# w65c265sxb_tms9118_dram_rev1.net
KiCad netlist of a schematic drawn in EAGLE
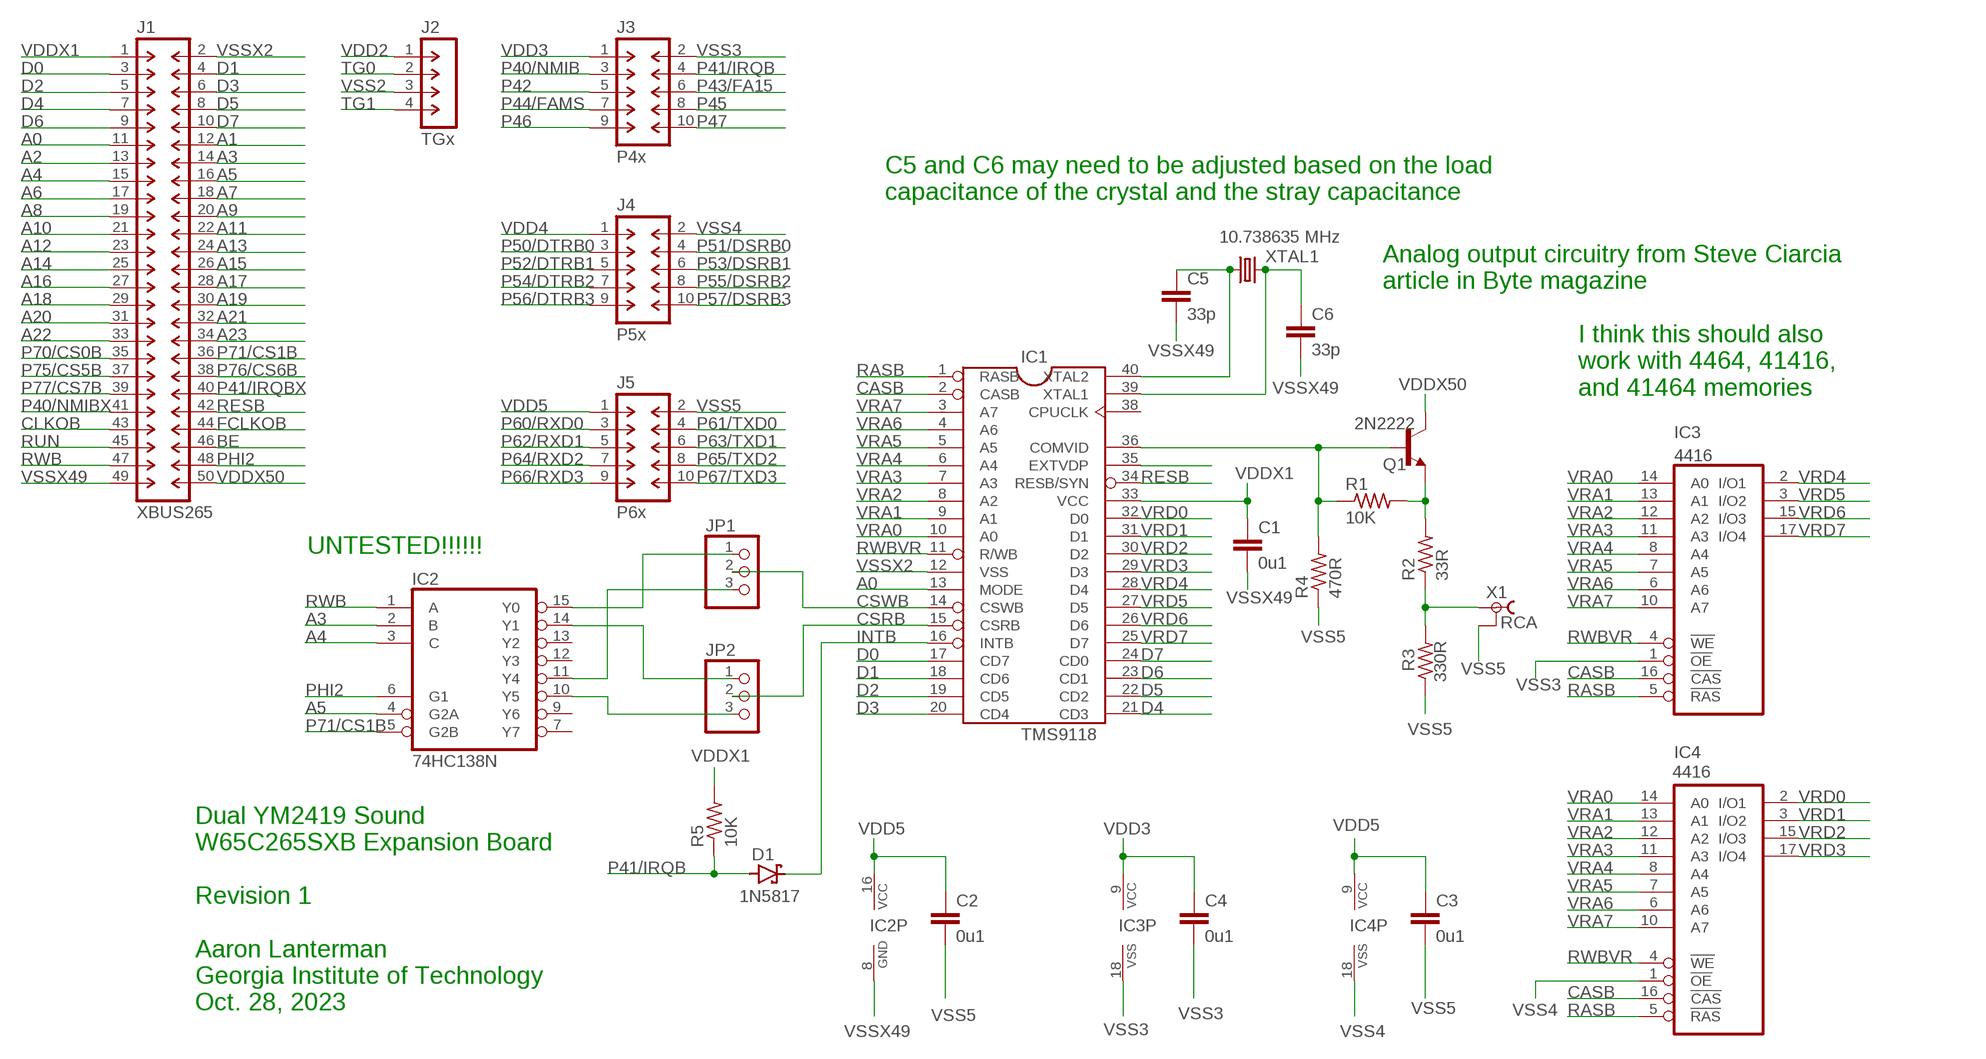
[diagram p0: schematic, sheet 1]

(export (version "E")
  (design (tool "Eeschema 10.0.6"))
  (components
    (comp (ref "C1")
      (value "0u1")
      (footprint "eagle-import:C050-025X075-AARON")
      (libsource (lib "eagle-import") (part "C-EU050-025X075-AARON"))
    )
    (comp (ref "C2")
      (value "0u1")
      (footprint "eagle-import:C050-025X075-AARON")
      (libsource (lib "eagle-import") (part "C-EU050-025X075-AARON"))
    )
    (comp (ref "C3")
      (value "0u1")
      (footprint "eagle-import:C050-025X075-AARON")
      (libsource (lib "eagle-import") (part "C-EU050-025X075-AARON"))
    )
    (comp (ref "C4")
      (value "0u1")
      (footprint "eagle-import:C050-025X075-AARON")
      (libsource (lib "eagle-import") (part "C-EU050-025X075-AARON"))
    )
    (comp (ref "C5")
      (value "33p")
      (footprint "eagle-import:C050-025X075-AARON")
      (libsource (lib "eagle-import") (part "C-EU050-025X075-AARON"))
    )
    (comp (ref "C6")
      (value "33p")
      (footprint "eagle-import:C050-025X075-AARON")
      (libsource (lib "eagle-import") (part "C-EU050-025X075-AARON"))
    )
    (comp (ref "D1")
      (value "1N5817-B")
      (footprint "eagle-import:DO41-7.6")
      (libsource (lib "eagle-import") (part "1N5817-B"))
    )
    (comp (ref "IC1")
      (value "TMS9118")
      (footprint "eagle-import:DIL40")
      (libsource (lib "eagle-import") (part "TMS9118"))
    )
    (comp (ref "IC2")
      (value "74HC138N")
      (footprint "eagle-import:DIL16")
      (libsource (lib "eagle-import") (part "74138NHC"))
    )
    (comp (ref "IC3")
      (value "41464")
      (footprint "eagle-import:DIL18")
      (libsource (lib "eagle-import") (part "41464"))
    )
    (comp (ref "IC4")
      (value "41464")
      (footprint "eagle-import:DIL18")
      (libsource (lib "eagle-import") (part "41464"))
    )
    (comp (ref "J1")
      (value "XBUS265")
      (footprint "eagle-import:DIL-100-2X25")
      (libsource (lib "eagle-import") (part "M-2X25-DIL-100"))
    )
    (comp (ref "J2")
      (value "TGx")
      (footprint "eagle-import:SIP-100-04-40")
      (libsource (lib "eagle-import") (part "M-1X04-SIP-100-40"))
    )
    (comp (ref "J3")
      (value "P4x")
      (footprint "eagle-import:DIL-100-2X05")
      (libsource (lib "eagle-import") (part "M-2X05-DIL-100"))
    )
    (comp (ref "J4")
      (value "P5x")
      (footprint "eagle-import:DIL-100-2X05")
      (libsource (lib "eagle-import") (part "M-2X05-DIL-100"))
    )
    (comp (ref "J5")
      (value "P6x")
      (footprint "eagle-import:DIL-100-2X05")
      (libsource (lib "eagle-import") (part "M-2X05-DIL-100"))
    )
    (comp (ref "JP1")
      (value "PINHD-1X3")
      (footprint "eagle-import:1X03")
      (libsource (lib "eagle-import") (part "PINHD-1X3"))
    )
    (comp (ref "JP2")
      (value "PINHD-1X3")
      (footprint "eagle-import:1X03")
      (libsource (lib "eagle-import") (part "PINHD-1X3"))
    )
    (comp (ref "Q1")
      (value "2N2222")
      (footprint "eagle-import:TO92-EBC-OVAL")
      (libsource (lib "eagle-import") (part "2N2222"))
    )
    (comp (ref "R1")
      (value "10K")
      (footprint "eagle-import:0207_10")
      (libsource (lib "eagle-import") (part "R-US_0207/10"))
    )
    (comp (ref "R2")
      (value "33R")
      (footprint "eagle-import:0207_10")
      (libsource (lib "eagle-import") (part "R-US_0207/10"))
    )
    (comp (ref "R3")
      (value "330R")
      (footprint "eagle-import:0207_10")
      (libsource (lib "eagle-import") (part "R-US_0207/10"))
    )
    (comp (ref "R4")
      (value "470R")
      (footprint "eagle-import:0207_10")
      (libsource (lib "eagle-import") (part "R-US_0207/10"))
    )
    (comp (ref "R5")
      (value "10K")
      (footprint "eagle-import:0207_10")
      (libsource (lib "eagle-import") (part "R-US_0207/10"))
    )
    (comp (ref "X1")
      (value "RCA")
      (footprint "eagle-import:TOBU3")
      (fields (field (name "MF") "FARNELL") (field (name "MPN") "TOBU 3"))
      (libsource (lib "eagle-import") (part "TOBU3"))
    )
    (comp (ref "XTAL1")
      (value "10.738635 MHz")
      (footprint "eagle-import:HC49_S")
      (libsource (lib "eagle-import") (part "CRYSTALHC49S"))
    )
  )
  (nets
    (net (code "1") (name "/A0") (class "Default")
      (node (ref "IC1") (pin "13") (pinfunction "MODE_13") (pintype "bidirectional"))
      (node (ref "J1") (pin "11") (pinfunction "11_11") (pintype "passive"))
    )
    (net (code "2") (name "/A1") (class "Default")
      (node (ref "J1") (pin "12") (pinfunction "12_12") (pintype "passive"))
    )
    (net (code "3") (name "/A2") (class "Default")
      (node (ref "J1") (pin "13") (pinfunction "13_13") (pintype "passive"))
    )
    (net (code "4") (name "/A3") (class "Default")
      (node (ref "IC2") (pin "2") (pinfunction "B_2") (pintype "input"))
      (node (ref "J1") (pin "14") (pinfunction "14_14") (pintype "passive"))
    )
    (net (code "5") (name "/A4") (class "Default")
      (node (ref "IC2") (pin "3") (pinfunction "C_3") (pintype "input"))
      (node (ref "J1") (pin "15") (pinfunction "15_15") (pintype "passive"))
    )
    (net (code "6") (name "/A5") (class "Default")
      (node (ref "IC2") (pin "4") (pinfunction "G2A_4") (pintype "input"))
      (node (ref "J1") (pin "16") (pinfunction "16_16") (pintype "passive"))
    )
    (net (code "7") (name "/A6") (class "Default")
      (node (ref "J1") (pin "17") (pinfunction "17_17") (pintype "passive"))
    )
    (net (code "8") (name "/A7") (class "Default")
      (node (ref "J1") (pin "18") (pinfunction "18_18") (pintype "passive"))
    )
    (net (code "9") (name "/A8") (class "Default")
      (node (ref "J1") (pin "19") (pinfunction "19_19") (pintype "passive"))
    )
    (net (code "10") (name "/A9") (class "Default")
      (node (ref "J1") (pin "20") (pinfunction "20_20") (pintype "passive"))
    )
    (net (code "11") (name "/A10") (class "Default")
      (node (ref "J1") (pin "21") (pinfunction "21_21") (pintype "passive"))
    )
    (net (code "12") (name "/A11") (class "Default")
      (node (ref "J1") (pin "22") (pinfunction "22_22") (pintype "passive"))
    )
    (net (code "13") (name "/A12") (class "Default")
      (node (ref "J1") (pin "23") (pinfunction "23_23") (pintype "passive"))
    )
    (net (code "14") (name "/A13") (class "Default")
      (node (ref "J1") (pin "24") (pinfunction "24_24") (pintype "passive"))
    )
    (net (code "15") (name "/A14") (class "Default")
      (node (ref "J1") (pin "25") (pinfunction "25_25") (pintype "passive"))
    )
    (net (code "16") (name "/A15") (class "Default")
      (node (ref "J1") (pin "26") (pinfunction "26_26") (pintype "passive"))
    )
    (net (code "17") (name "/A16") (class "Default")
      (node (ref "J1") (pin "27") (pinfunction "27_27") (pintype "passive"))
    )
    (net (code "18") (name "/A17") (class "Default")
      (node (ref "J1") (pin "28") (pinfunction "28_28") (pintype "passive"))
    )
    (net (code "19") (name "/A18") (class "Default")
      (node (ref "J1") (pin "29") (pinfunction "29_29") (pintype "passive"))
    )
    (net (code "20") (name "/A19") (class "Default")
      (node (ref "J1") (pin "30") (pinfunction "30_30") (pintype "passive"))
    )
    (net (code "21") (name "/A20") (class "Default")
      (node (ref "J1") (pin "31") (pinfunction "31_31") (pintype "passive"))
    )
    (net (code "22") (name "/A21") (class "Default")
      (node (ref "J1") (pin "32") (pinfunction "32_32") (pintype "passive"))
    )
    (net (code "23") (name "/A22") (class "Default")
      (node (ref "J1") (pin "33") (pinfunction "33_33") (pintype "passive"))
    )
    (net (code "24") (name "/A23") (class "Default")
      (node (ref "J1") (pin "34") (pinfunction "34_34") (pintype "passive"))
    )
    (net (code "25") (name "/BE") (class "Default")
      (node (ref "J1") (pin "46") (pinfunction "46_46") (pintype "passive"))
    )
    (net (code "26") (name "/CASB") (class "Default")
      (node (ref "IC1") (pin "2") (pinfunction "CASB_2") (pintype "bidirectional"))
      (node (ref "IC3") (pin "16") (pinfunction "~{CAS}_16") (pintype "input"))
      (node (ref "IC4") (pin "16") (pinfunction "~{CAS}_16") (pintype "input"))
    )
    (net (code "27") (name "/CLKOB") (class "Default")
      (node (ref "J1") (pin "43") (pinfunction "43_43") (pintype "passive"))
    )
    (net (code "28") (name "/CSRB") (class "Default")
      (node (ref "IC1") (pin "15") (pinfunction "CSRB_15") (pintype "bidirectional"))
      (node (ref "JP2") (pin "2") (pinfunction "2_2") (pintype "passive"))
    )
    (net (code "29") (name "/CSWB") (class "Default")
      (node (ref "IC1") (pin "14") (pinfunction "CSWB_14") (pintype "bidirectional"))
      (node (ref "JP1") (pin "2") (pinfunction "2_2") (pintype "passive"))
    )
    (net (code "30") (name "/D0") (class "Default")
      (node (ref "IC1") (pin "17") (pinfunction "CD7_17") (pintype "bidirectional"))
      (node (ref "J1") (pin "3") (pinfunction "3_3") (pintype "passive"))
    )
    (net (code "31") (name "/D1") (class "Default")
      (node (ref "IC1") (pin "18") (pinfunction "CD6_18") (pintype "bidirectional"))
      (node (ref "J1") (pin "4") (pinfunction "4_4") (pintype "passive"))
    )
    (net (code "32") (name "/D2") (class "Default")
      (node (ref "IC1") (pin "19") (pinfunction "CD5_19") (pintype "bidirectional"))
      (node (ref "J1") (pin "5") (pinfunction "5_5") (pintype "passive"))
    )
    (net (code "33") (name "/D3") (class "Default")
      (node (ref "IC1") (pin "20") (pinfunction "CD4_20") (pintype "bidirectional"))
      (node (ref "J1") (pin "6") (pinfunction "6_6") (pintype "passive"))
    )
    (net (code "34") (name "/D4") (class "Default")
      (node (ref "IC1") (pin "21") (pinfunction "CD3_21") (pintype "bidirectional"))
      (node (ref "J1") (pin "7") (pinfunction "7_7") (pintype "passive"))
    )
    (net (code "35") (name "/D5") (class "Default")
      (node (ref "IC1") (pin "22") (pinfunction "CD2_22") (pintype "bidirectional"))
      (node (ref "J1") (pin "8") (pinfunction "8_8") (pintype "passive"))
    )
    (net (code "36") (name "/D6") (class "Default")
      (node (ref "IC1") (pin "23") (pinfunction "CD1_23") (pintype "bidirectional"))
      (node (ref "J1") (pin "9") (pinfunction "9_9") (pintype "passive"))
    )
    (net (code "37") (name "/D7") (class "Default")
      (node (ref "IC1") (pin "24") (pinfunction "CD0_24") (pintype "bidirectional"))
      (node (ref "J1") (pin "10") (pinfunction "10_10") (pintype "passive"))
    )
    (net (code "38") (name "/FCLKOB") (class "Default")
      (node (ref "J1") (pin "44") (pinfunction "44_44") (pintype "passive"))
    )
    (net (code "39") (name "/INTB") (class "Default")
      (node (ref "D1") (pin "C") (pinfunction "C_C") (pintype "passive"))
      (node (ref "IC1") (pin "16") (pinfunction "INTB_16") (pintype "bidirectional"))
    )
    (net (code "40") (name "/P40{slash}NMIB") (class "Default")
      (node (ref "J3") (pin "3") (pinfunction "3_3") (pintype "passive"))
    )
    (net (code "41") (name "/P40{slash}NMIBX") (class "Default")
      (node (ref "J1") (pin "41") (pinfunction "41_41") (pintype "passive"))
    )
    (net (code "42") (name "/P41{slash}IRQB") (class "Default")
      (node (ref "D1") (pin "A") (pinfunction "A_A") (pintype "passive"))
      (node (ref "J3") (pin "4") (pinfunction "4_4") (pintype "passive"))
      (node (ref "R5") (pin "1") (pinfunction "1_1") (pintype "passive"))
    )
    (net (code "43") (name "/P41{slash}IRQBX") (class "Default")
      (node (ref "J1") (pin "40") (pinfunction "40_40") (pintype "passive"))
    )
    (net (code "44") (name "/P42") (class "Default")
      (node (ref "J3") (pin "5") (pinfunction "5_5") (pintype "passive"))
    )
    (net (code "45") (name "/P43{slash}FA15") (class "Default")
      (node (ref "J3") (pin "6") (pinfunction "6_6") (pintype "passive"))
    )
    (net (code "46") (name "/P44{slash}FAMS") (class "Default")
      (node (ref "J3") (pin "7") (pinfunction "7_7") (pintype "passive"))
    )
    (net (code "47") (name "/P45") (class "Default")
      (node (ref "J3") (pin "8") (pinfunction "8_8") (pintype "passive"))
    )
    (net (code "48") (name "/P46") (class "Default")
      (node (ref "J3") (pin "9") (pinfunction "9_9") (pintype "passive"))
    )
    (net (code "49") (name "/P47") (class "Default")
      (node (ref "J3") (pin "10") (pinfunction "10_10") (pintype "passive"))
    )
    (net (code "50") (name "/P50{slash}DTRB0") (class "Default")
      (node (ref "J4") (pin "3") (pinfunction "3_3") (pintype "passive"))
    )
    (net (code "51") (name "/P51{slash}DSRB0") (class "Default")
      (node (ref "J4") (pin "4") (pinfunction "4_4") (pintype "passive"))
    )
    (net (code "52") (name "/P52{slash}DTRB1") (class "Default")
      (node (ref "J4") (pin "5") (pinfunction "5_5") (pintype "passive"))
    )
    (net (code "53") (name "/P53{slash}DSRB1") (class "Default")
      (node (ref "J4") (pin "6") (pinfunction "6_6") (pintype "passive"))
    )
    (net (code "54") (name "/P54{slash}DTRB2") (class "Default")
      (node (ref "J4") (pin "7") (pinfunction "7_7") (pintype "passive"))
    )
    (net (code "55") (name "/P55{slash}DSRB2") (class "Default")
      (node (ref "J4") (pin "8") (pinfunction "8_8") (pintype "passive"))
    )
    (net (code "56") (name "/P56{slash}DTRB3") (class "Default")
      (node (ref "J4") (pin "9") (pinfunction "9_9") (pintype "passive"))
    )
    (net (code "57") (name "/P57{slash}DSRB3") (class "Default")
      (node (ref "J4") (pin "10") (pinfunction "10_10") (pintype "passive"))
    )
    (net (code "58") (name "/P60{slash}RXD0") (class "Default")
      (node (ref "J5") (pin "3") (pinfunction "3_3") (pintype "passive"))
    )
    (net (code "59") (name "/P61{slash}TXD0") (class "Default")
      (node (ref "J5") (pin "4") (pinfunction "4_4") (pintype "passive"))
    )
    (net (code "60") (name "/P62{slash}RXD1") (class "Default")
      (node (ref "J5") (pin "5") (pinfunction "5_5") (pintype "passive"))
    )
    (net (code "61") (name "/P63{slash}TXD1") (class "Default")
      (node (ref "J5") (pin "6") (pinfunction "6_6") (pintype "passive"))
    )
    (net (code "62") (name "/P64{slash}RXD2") (class "Default")
      (node (ref "J5") (pin "7") (pinfunction "7_7") (pintype "passive"))
    )
    (net (code "63") (name "/P65{slash}TXD2") (class "Default")
      (node (ref "J5") (pin "8") (pinfunction "8_8") (pintype "passive"))
    )
    (net (code "64") (name "/P66{slash}RXD3") (class "Default")
      (node (ref "J5") (pin "9") (pinfunction "9_9") (pintype "passive"))
    )
    (net (code "65") (name "/P67{slash}TXD3") (class "Default")
      (node (ref "J5") (pin "10") (pinfunction "10_10") (pintype "passive"))
    )
    (net (code "66") (name "/P70{slash}CS0B") (class "Default")
      (node (ref "J1") (pin "35") (pinfunction "35_35") (pintype "passive"))
    )
    (net (code "67") (name "/P71{slash}CS1B") (class "Default")
      (node (ref "IC2") (pin "5") (pinfunction "G2B_5") (pintype "input"))
      (node (ref "J1") (pin "36") (pinfunction "36_36") (pintype "passive"))
    )
    (net (code "68") (name "/P75{slash}CS5B") (class "Default")
      (node (ref "J1") (pin "37") (pinfunction "37_37") (pintype "passive"))
    )
    (net (code "69") (name "/P76{slash}CS6B") (class "Default")
      (node (ref "J1") (pin "38") (pinfunction "38_38") (pintype "passive"))
    )
    (net (code "70") (name "/P77{slash}CS7B") (class "Default")
      (node (ref "J1") (pin "39") (pinfunction "39_39") (pintype "passive"))
    )
    (net (code "71") (name "/PHI2") (class "Default")
      (node (ref "IC2") (pin "6") (pinfunction "G1_6") (pintype "input"))
      (node (ref "J1") (pin "48") (pinfunction "48_48") (pintype "passive"))
    )
    (net (code "72") (name "/RASB") (class "Default")
      (node (ref "IC1") (pin "1") (pinfunction "RASB_1") (pintype "bidirectional"))
      (node (ref "IC3") (pin "5") (pinfunction "~{RAS}_5") (pintype "input"))
      (node (ref "IC4") (pin "5") (pinfunction "~{RAS}_5") (pintype "input"))
    )
    (net (code "73") (name "/RESB") (class "Default")
      (node (ref "IC1") (pin "34") (pinfunction "RESB/SYN_34") (pintype "bidirectional"))
      (node (ref "J1") (pin "42") (pinfunction "42_42") (pintype "passive"))
    )
    (net (code "74") (name "/RUN") (class "Default")
      (node (ref "J1") (pin "45") (pinfunction "45_45") (pintype "passive"))
    )
    (net (code "75") (name "/RWB") (class "Default")
      (node (ref "IC2") (pin "1") (pinfunction "A_1") (pintype "input"))
      (node (ref "J1") (pin "47") (pinfunction "47_47") (pintype "passive"))
    )
    (net (code "76") (name "/RWBVR") (class "Default")
      (node (ref "IC1") (pin "11") (pinfunction "R/WB_11") (pintype "bidirectional"))
      (node (ref "IC3") (pin "4") (pinfunction "~{WE}_4") (pintype "input"))
      (node (ref "IC4") (pin "4") (pinfunction "~{WE}_4") (pintype "input"))
    )
    (net (code "77") (name "/TG0") (class "Default")
      (node (ref "J2") (pin "2") (pinfunction "2_2") (pintype "passive"))
    )
    (net (code "78") (name "/TG1") (class "Default")
      (node (ref "J2") (pin "4") (pinfunction "4_4") (pintype "passive"))
    )
    (net (code "79") (name "/VDD2") (class "Default")
      (node (ref "J2") (pin "1") (pinfunction "1_1") (pintype "passive"))
    )
    (net (code "80") (name "/VDD3") (class "Default")
      (node (ref "C4") (pin "1") (pinfunction "1_1") (pintype "passive"))
      (node (ref "IC3") (pin "9") (pinfunction "VCC_9") (pintype "power_in"))
      (node (ref "J3") (pin "1") (pinfunction "1_1") (pintype "passive"))
    )
    (net (code "81") (name "/VDD4") (class "Default")
      (node (ref "J4") (pin "1") (pinfunction "1_1") (pintype "passive"))
    )
    (net (code "82") (name "/VDD5") (class "Default")
      (node (ref "C2") (pin "1") (pinfunction "1_1") (pintype "passive"))
      (node (ref "C3") (pin "1") (pinfunction "1_1") (pintype "passive"))
      (node (ref "IC2") (pin "16") (pinfunction "VCC_16") (pintype "power_in"))
      (node (ref "IC4") (pin "9") (pinfunction "VCC_9") (pintype "power_in"))
      (node (ref "J5") (pin "1") (pinfunction "1_1") (pintype "passive"))
    )
    (net (code "83") (name "/VDDX1") (class "Default")
      (node (ref "C1") (pin "1") (pinfunction "1_1") (pintype "passive"))
      (node (ref "IC1") (pin "33") (pinfunction "VCC_33") (pintype "bidirectional"))
      (node (ref "J1") (pin "1") (pinfunction "1_1") (pintype "passive"))
      (node (ref "R5") (pin "2") (pinfunction "2_2") (pintype "passive"))
    )
    (net (code "84") (name "/VDDX50") (class "Default")
      (node (ref "J1") (pin "50") (pinfunction "50_50") (pintype "passive"))
      (node (ref "Q1") (pin "C") (pinfunction "C_C") (pintype "passive"))
    )
    (net (code "85") (name "/VRA0") (class "Default")
      (node (ref "IC1") (pin "10") (pinfunction "A0_10") (pintype "bidirectional"))
      (node (ref "IC3") (pin "14") (pinfunction "A0_14") (pintype "input"))
      (node (ref "IC4") (pin "14") (pinfunction "A0_14") (pintype "input"))
    )
    (net (code "86") (name "/VRA1") (class "Default")
      (node (ref "IC1") (pin "9") (pinfunction "A1_9") (pintype "bidirectional"))
      (node (ref "IC3") (pin "13") (pinfunction "A1_13") (pintype "input"))
      (node (ref "IC4") (pin "13") (pinfunction "A1_13") (pintype "input"))
    )
    (net (code "87") (name "/VRA2") (class "Default")
      (node (ref "IC1") (pin "8") (pinfunction "A2_8") (pintype "bidirectional"))
      (node (ref "IC3") (pin "12") (pinfunction "A2_12") (pintype "input"))
      (node (ref "IC4") (pin "12") (pinfunction "A2_12") (pintype "input"))
    )
    (net (code "88") (name "/VRA3") (class "Default")
      (node (ref "IC1") (pin "7") (pinfunction "A3_7") (pintype "bidirectional"))
      (node (ref "IC3") (pin "11") (pinfunction "A3_11") (pintype "input"))
      (node (ref "IC4") (pin "11") (pinfunction "A3_11") (pintype "input"))
    )
    (net (code "89") (name "/VRA4") (class "Default")
      (node (ref "IC1") (pin "6") (pinfunction "A4_6") (pintype "bidirectional"))
      (node (ref "IC3") (pin "8") (pinfunction "A4_8") (pintype "input"))
      (node (ref "IC4") (pin "8") (pinfunction "A4_8") (pintype "input"))
    )
    (net (code "90") (name "/VRA5") (class "Default")
      (node (ref "IC1") (pin "5") (pinfunction "A5_5") (pintype "bidirectional"))
      (node (ref "IC3") (pin "7") (pinfunction "A5_7") (pintype "input"))
      (node (ref "IC4") (pin "7") (pinfunction "A5_7") (pintype "input"))
    )
    (net (code "91") (name "/VRA6") (class "Default")
      (node (ref "IC1") (pin "4") (pinfunction "A6_4") (pintype "bidirectional"))
      (node (ref "IC3") (pin "6") (pinfunction "A6_6") (pintype "input"))
      (node (ref "IC4") (pin "6") (pinfunction "A6_6") (pintype "input"))
    )
    (net (code "92") (name "/VRA7") (class "Default")
      (node (ref "IC1") (pin "3") (pinfunction "A7_3") (pintype "bidirectional"))
      (node (ref "IC3") (pin "10") (pinfunction "A7_10") (pintype "input"))
      (node (ref "IC4") (pin "10") (pinfunction "A7_10") (pintype "input"))
    )
    (net (code "93") (name "/VRD0") (class "Default")
      (node (ref "IC1") (pin "32") (pinfunction "D0_32") (pintype "bidirectional"))
      (node (ref "IC4") (pin "2") (pinfunction "I/O1_2") (pintype "bidirectional"))
    )
    (net (code "94") (name "/VRD1") (class "Default")
      (node (ref "IC1") (pin "31") (pinfunction "D1_31") (pintype "bidirectional"))
      (node (ref "IC4") (pin "3") (pinfunction "I/O2_3") (pintype "bidirectional"))
    )
    (net (code "95") (name "/VRD2") (class "Default")
      (node (ref "IC1") (pin "30") (pinfunction "D2_30") (pintype "bidirectional"))
      (node (ref "IC4") (pin "15") (pinfunction "I/O3_15") (pintype "bidirectional"))
    )
    (net (code "96") (name "/VRD3") (class "Default")
      (node (ref "IC1") (pin "29") (pinfunction "D3_29") (pintype "bidirectional"))
      (node (ref "IC4") (pin "17") (pinfunction "I/O4_17") (pintype "bidirectional"))
    )
    (net (code "97") (name "/VRD4") (class "Default")
      (node (ref "IC1") (pin "28") (pinfunction "D4_28") (pintype "bidirectional"))
      (node (ref "IC3") (pin "2") (pinfunction "I/O1_2") (pintype "bidirectional"))
    )
    (net (code "98") (name "/VRD5") (class "Default")
      (node (ref "IC1") (pin "27") (pinfunction "D5_27") (pintype "bidirectional"))
      (node (ref "IC3") (pin "3") (pinfunction "I/O2_3") (pintype "bidirectional"))
    )
    (net (code "99") (name "/VRD6") (class "Default")
      (node (ref "IC1") (pin "26") (pinfunction "D6_26") (pintype "bidirectional"))
      (node (ref "IC3") (pin "15") (pinfunction "I/O3_15") (pintype "bidirectional"))
    )
    (net (code "100") (name "/VRD7") (class "Default")
      (node (ref "IC1") (pin "25") (pinfunction "D7_25") (pintype "bidirectional"))
      (node (ref "IC3") (pin "17") (pinfunction "I/O4_17") (pintype "bidirectional"))
    )
    (net (code "101") (name "/VSS2") (class "Default")
      (node (ref "J2") (pin "3") (pinfunction "3_3") (pintype "passive"))
    )
    (net (code "102") (name "/VSS3") (class "Default")
      (node (ref "C4") (pin "2") (pinfunction "2_2") (pintype "passive"))
      (node (ref "IC3") (pin "1") (pinfunction "~{OE}_1") (pintype "input"))
      (node (ref "IC3") (pin "18") (pinfunction "VSS_18") (pintype "power_in"))
      (node (ref "J3") (pin "2") (pinfunction "2_2") (pintype "passive"))
    )
    (net (code "103") (name "/VSS4") (class "Default")
      (node (ref "IC4") (pin "1") (pinfunction "~{OE}_1") (pintype "input"))
      (node (ref "IC4") (pin "18") (pinfunction "VSS_18") (pintype "power_in"))
      (node (ref "J4") (pin "2") (pinfunction "2_2") (pintype "passive"))
    )
    (net (code "104") (name "/VSS5") (class "Default")
      (node (ref "C2") (pin "2") (pinfunction "2_2") (pintype "passive"))
      (node (ref "C3") (pin "2") (pinfunction "2_2") (pintype "passive"))
      (node (ref "J5") (pin "2") (pinfunction "2_2") (pintype "passive"))
      (node (ref "R3") (pin "1") (pinfunction "1_1") (pintype "passive"))
      (node (ref "R4") (pin "1") (pinfunction "1_1") (pintype "passive"))
      (node (ref "X1") (pin "2") (pinfunction "2_2") (pintype "passive"))
      (node (ref "X1") (pin "2@1") (pinfunction "2_2@1") (pintype "passive"))
      (node (ref "X1") (pin "2@2") (pinfunction "2_2@2") (pintype "passive"))
    )
    (net (code "105") (name "/VSSX2") (class "Default")
      (node (ref "IC1") (pin "12") (pinfunction "VSS_12") (pintype "bidirectional"))
      (node (ref "J1") (pin "2") (pinfunction "2_2") (pintype "passive"))
    )
    (net (code "106") (name "/VSSX49") (class "Default")
      (node (ref "C1") (pin "2") (pinfunction "2_2") (pintype "passive"))
      (node (ref "C5") (pin "2") (pinfunction "2_2") (pintype "passive"))
      (node (ref "C6") (pin "2") (pinfunction "2_2") (pintype "passive"))
      (node (ref "IC2") (pin "8") (pinfunction "GND_8") (pintype "power_in"))
      (node (ref "J1") (pin "49") (pinfunction "49_49") (pintype "passive"))
    )
    (net (code "107") (name "Net-(IC1-COMVID)") (class "Default")
      (node (ref "IC1") (pin "36") (pinfunction "COMVID_36") (pintype "bidirectional"))
      (node (ref "Q1") (pin "B") (pinfunction "B_B") (pintype "passive"))
      (node (ref "R1") (pin "1") (pinfunction "1_1") (pintype "passive"))
      (node (ref "R4") (pin "2") (pinfunction "2_2") (pintype "passive"))
    )
    (net (code "108") (name "Net-(IC1-XTAL1)") (class "Default")
      (node (ref "C6") (pin "1") (pinfunction "1_1") (pintype "passive"))
      (node (ref "IC1") (pin "39") (pinfunction "XTAL1_39") (pintype "bidirectional"))
      (node (ref "XTAL1") (pin "2") (pinfunction "2_2") (pintype "passive"))
    )
    (net (code "109") (name "Net-(IC1-XTAL2)") (class "Default")
      (node (ref "C5") (pin "1") (pinfunction "1_1") (pintype "passive"))
      (node (ref "IC1") (pin "40") (pinfunction "XTAL2_40") (pintype "bidirectional"))
      (node (ref "XTAL1") (pin "1") (pinfunction "1_1") (pintype "passive"))
    )
    (net (code "110") (name "Net-(IC2A-Y0)") (class "Default")
      (node (ref "IC2") (pin "15") (pinfunction "Y0_15") (pintype "output"))
      (node (ref "JP1") (pin "1") (pinfunction "1_1") (pintype "passive"))
    )
    (net (code "111") (name "Net-(IC2A-Y1)") (class "Default")
      (node (ref "IC2") (pin "14") (pinfunction "Y1_14") (pintype "output"))
      (node (ref "JP2") (pin "1") (pinfunction "1_1") (pintype "passive"))
    )
    (net (code "112") (name "Net-(IC2A-Y4)") (class "Default")
      (node (ref "IC2") (pin "11") (pinfunction "Y4_11") (pintype "output"))
      (node (ref "JP1") (pin "3") (pinfunction "3_3") (pintype "passive"))
    )
    (net (code "113") (name "Net-(IC2A-Y5)") (class "Default")
      (node (ref "IC2") (pin "10") (pinfunction "Y5_10") (pintype "output"))
      (node (ref "JP2") (pin "3") (pinfunction "3_3") (pintype "passive"))
    )
    (net (code "114") (name "Net-(Q1-PadE)") (class "Default")
      (node (ref "Q1") (pin "E") (pinfunction "E_E") (pintype "passive"))
      (node (ref "R1") (pin "2") (pinfunction "2_2") (pintype "passive"))
      (node (ref "R2") (pin "2") (pinfunction "2_2") (pintype "passive"))
    )
    (net (code "115") (name "Net-(R2-Pad1)") (class "Default")
      (node (ref "R2") (pin "1") (pinfunction "1_1") (pintype "passive"))
      (node (ref "R3") (pin "2") (pinfunction "2_2") (pintype "passive"))
      (node (ref "X1") (pin "1") (pinfunction "1_1") (pintype "passive"))
    )
    (net (code "116") (name "unconnected-(IC1-CPUCLK-Pad38)") (class "Default")
      (node (ref "IC1") (pin "38") (pinfunction "CPUCLK_38") (pintype "bidirectional"))
    )
    (net (code "117") (name "unconnected-(IC1-EXTVDP-Pad35)") (class "Default")
      (node (ref "IC1") (pin "35") (pinfunction "EXTVDP_35") (pintype "bidirectional"))
    )
    (net (code "118") (name "unconnected-(IC2A-Y2-Pad13)") (class "Default")
      (node (ref "IC2") (pin "13") (pinfunction "Y2_13") (pintype "output"))
    )
    (net (code "119") (name "unconnected-(IC2A-Y3-Pad12)") (class "Default")
      (node (ref "IC2") (pin "12") (pinfunction "Y3_12") (pintype "output"))
    )
    (net (code "120") (name "unconnected-(IC2A-Y6-Pad9)") (class "Default")
      (node (ref "IC2") (pin "9") (pinfunction "Y6_9") (pintype "output"))
    )
    (net (code "121") (name "unconnected-(IC2A-Y7-Pad7)") (class "Default")
      (node (ref "IC2") (pin "7") (pinfunction "Y7_7") (pintype "output"))
    )
  )
)
